# impulse.net
KiCad netlist of a schematic drawn in Altium Designer
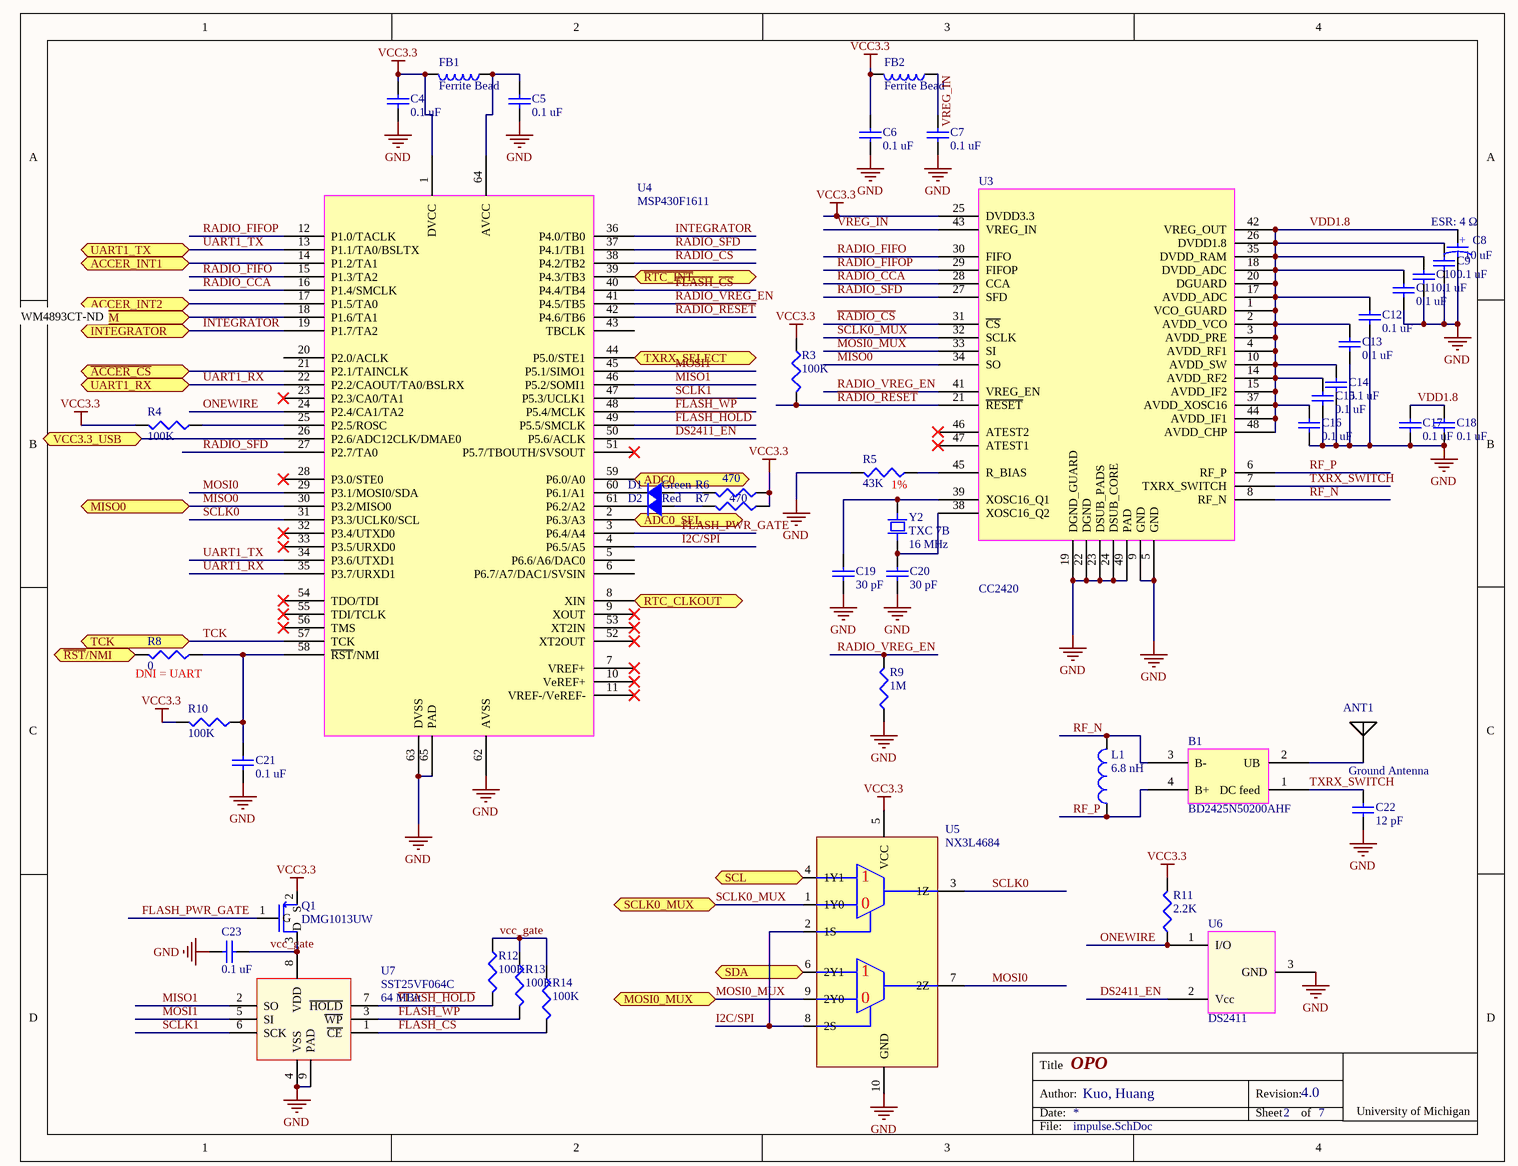
[diagram p0: impulse.SchDoc]

(export (version "E")
  (design (tool "Eeschema 10.0.6"))
  (components
    (comp (ref "ANT1")
      (value "Ground Antenna")
      (footprint "Chip Antenna")
      (description "2.4GHz Surface Mount Device (SMD) On Ground Antenna, 50 Ohms")
      (libsource (lib "opo") (part "Ground Antenna"))
    )
    (comp (ref "B1")
      (value "BD2425N50200AHF")
      (footprint "BD2425N50200AHF")
      (description "Ultra Low Profile 0404 Balun   50Ω to 200Ω Balanced")
      (libsource (lib "opo") (part "BD2425N50200AHF"))
    )
    (comp (ref "C4")
      (value "0.1 uF")
      (footprint "0402")
      (description "Ceramic capacitor, 0.1u, 0402 package")
      (fields (field (name "TOLERANCE") "10%") (field (name "Comment") "Ceramic capacitor"))
      (libsource (lib "rlc") (part "C_0.1u_0402_ceramic"))
    )
    (comp (ref "C5")
      (value "0.1 uF")
      (footprint "0402")
      (description "Ceramic capacitor, 0.1u, 0402 package")
      (fields (field (name "TOLERANCE") "10%") (field (name "Comment") "Ceramic capacitor"))
      (libsource (lib "rlc") (part "C_0.1u_0402_ceramic"))
    )
    (comp (ref "C6")
      (value "0.1 uF")
      (footprint "0402")
      (description "Ceramic capacitor, 0.1u, 0402 package")
      (fields (field (name "TOLERANCE") "10%") (field (name "Comment") "Ceramic capacitor"))
      (libsource (lib "rlc") (part "C_0.1u_0402_ceramic"))
    )
    (comp (ref "C7")
      (value "0.1 uF")
      (footprint "0402")
      (description "Ceramic capacitor, 0.1u, 0402 package")
      (fields (field (name "TOLERANCE") "10%") (field (name "Comment") "Ceramic capacitor"))
      (libsource (lib "rlc") (part "C_0.1u_0402_ceramic"))
    )
    (comp (ref "C8")
      (value "10 uF")
      (footprint "0603 - Polar Marking")
      (description "Tantalum capacitor, 10 uF, 0603 package")
      (fields
        (field (name "TOLERANCE") "10%")
        (field (name "ESR") "4 Ω")
        (field (name "Comment") "Tantalum capacitor")
      )
      (libsource (lib "rlc") (part "C_10u_0603_tantalum"))
    )
    (comp (ref "C9")
      (value "0.1 uF")
      (footprint "0402")
      (description "Ceramic capacitor, 0.1u, 0402 package")
      (fields (field (name "TOLERANCE") "10%") (field (name "Comment") "Ceramic capacitor"))
      (libsource (lib "rlc") (part "C_0.1u_0402_ceramic"))
    )
    (comp (ref "C10")
      (value "0.1 uF")
      (footprint "0402")
      (description "Ceramic capacitor, 0.1u, 0402 package")
      (fields (field (name "TOLERANCE") "10%") (field (name "Comment") "Ceramic capacitor"))
      (libsource (lib "rlc") (part "C_0.1u_0402_ceramic"))
    )
    (comp (ref "C11")
      (value "0.1 uF")
      (footprint "0402")
      (description "Ceramic capacitor, 0.1u, 0402 package")
      (fields (field (name "TOLERANCE") "10%") (field (name "Comment") "Ceramic capacitor"))
      (libsource (lib "rlc") (part "C_0.1u_0402_ceramic"))
    )
    (comp (ref "C12")
      (value "0.1 uF")
      (footprint "0402")
      (description "Ceramic capacitor, 0.1u, 0402 package")
      (fields (field (name "TOLERANCE") "10%") (field (name "Comment") "Ceramic capacitor"))
      (libsource (lib "rlc") (part "C_0.1u_0402_ceramic"))
    )
    (comp (ref "C13")
      (value "0.1 uF")
      (footprint "0402")
      (description "Ceramic capacitor, 0.1u, 0402 package")
      (fields (field (name "TOLERANCE") "10%") (field (name "Comment") "Ceramic capacitor"))
      (libsource (lib "rlc") (part "C_0.1u_0402_ceramic"))
    )
    (comp (ref "C14")
      (value "0.1 uF")
      (footprint "0402")
      (description "Ceramic capacitor, 0.1u, 0402 package")
      (fields (field (name "TOLERANCE") "10%") (field (name "Comment") "Ceramic capacitor"))
      (libsource (lib "rlc") (part "C_0.1u_0402_ceramic"))
    )
    (comp (ref "C15")
      (value "0.1 uF")
      (footprint "0402")
      (description "Ceramic capacitor, 0.1u, 0402 package")
      (fields (field (name "TOLERANCE") "10%") (field (name "Comment") "Ceramic capacitor"))
      (libsource (lib "rlc") (part "C_0.1u_0402_ceramic"))
    )
    (comp (ref "C16")
      (value "0.1 uF")
      (footprint "0402")
      (description "Ceramic capacitor, 0.1u, 0402 package")
      (fields (field (name "TOLERANCE") "10%") (field (name "Comment") "Ceramic capacitor"))
      (libsource (lib "rlc") (part "C_0.1u_0402_ceramic"))
    )
    (comp (ref "C17")
      (value "0.1 uF")
      (footprint "0402")
      (description "Ceramic capacitor, 0.1u, 0402 package")
      (fields (field (name "TOLERANCE") "10%") (field (name "Comment") "Ceramic capacitor"))
      (libsource (lib "rlc") (part "C_0.1u_0402_ceramic"))
    )
    (comp (ref "C18")
      (value "0.1 uF")
      (footprint "0402")
      (description "Ceramic capacitor, 0.1u, 0402 package")
      (fields (field (name "TOLERANCE") "10%") (field (name "Comment") "Ceramic capacitor"))
      (libsource (lib "rlc") (part "C_0.1u_0402_ceramic"))
    )
    (comp (ref "C19")
      (value "30 pF")
      (footprint "0402")
      (description "Ceramic capacitor, 30 pF, 0402 package")
      (fields (field (name "TOLERANCE") "2%") (field (name "Comment") "Ceramic capacitor"))
      (libsource (lib "rlc") (part "C_30p_0402_ceramic"))
    )
    (comp (ref "C20")
      (value "30 pF")
      (footprint "0402")
      (description "Ceramic capacitor, 30 pF, 0402 package")
      (fields (field (name "TOLERANCE") "2%") (field (name "Comment") "Ceramic capacitor"))
      (libsource (lib "rlc") (part "C_30p_0402_ceramic"))
    )
    (comp (ref "C21")
      (value "0.1 uF")
      (footprint "0402")
      (description "Ceramic capacitor, 0.1u, 0402 package")
      (fields (field (name "TOLERANCE") "10%") (field (name "Comment") "Ceramic capacitor"))
      (libsource (lib "rlc") (part "C_0.1u_0402_ceramic"))
    )
    (comp (ref "C22")
      (value "12 pF")
      (footprint "0402")
      (description "Ceramic capacitor, 12 pF, 0402 package")
      (fields (field (name "TOLERANCE") "2%") (field (name "Comment") "Ceramic capacitor"))
      (libsource (lib "rlc") (part "C_12p_0402_ceramic"))
    )
    (comp (ref "C23")
      (value "0.1 uF")
      (footprint "0402")
      (description "Ceramic capacitor, 0.1u, 0402 package")
      (fields (field (name "TOLERANCE") "10%") (field (name "Comment") "Ceramic capacitor"))
      (libsource (lib "rlc") (part "C_0.1u_0402_ceramic"))
    )
    (comp (ref "D1")
      (value "LED, Green")
      (footprint "0402 - DIODE")
      (description "LED, Green,  0402")
      (fields (field (name "COLOR") "Green"))
      (libsource (lib "rlc") (part "D_LED_GREEN_0402"))
    )
    (comp (ref "D2")
      (value "LED, Red")
      (footprint "0402 - DIODE")
      (description "LED, Red, 0402")
      (fields (field (name "COLOR") "Red"))
      (libsource (lib "rlc") (part "D_LED_RED_0402"))
    )
    (comp (ref "FB1")
      (value "Ferrite Bead")
      (footprint "0402")
      (description "Ferrite Bead, 150 mA, 0402 package")
      (libsource (lib "rlc") (part "FB_150mA_0402"))
    )
    (comp (ref "FB2")
      (value "Ferrite Bead")
      (footprint "0402")
      (description "Ferrite Bead, 150 mA, 0402 package")
      (libsource (lib "rlc") (part "FB_150mA_0402"))
    )
    (comp (ref "L1")
      (value "6.8 nH")
      (footprint "0402")
      (description "Chip inductor, 6.8 nH, 0402 package")
      (fields (field (name "TOLERANCE") "5%") (field (name "Comment") "Chip inductor"))
      (libsource (lib "rlc") (part "L_6.8n_0402"))
    )
    (comp (ref "Q1")
      (value "DMG1013UW")
      (footprint "SC70-3")
      (description "P-CHANNEL ENHANCEMENT MODE MOSFET")
      (libsource (lib "opo") (part "DMG1013UW"))
    )
    (comp (ref "R3")
      (value "100K")
      (footprint "0402")
      (description "Chip resistor, 100K, 0402 package")
      (fields (field (name "TOLERANCE") "1%") (field (name "POWER") "1/16 W"))
      (libsource (lib "rlc") (part "R_100K_0402"))
    )
    (comp (ref "R4")
      (value "100K")
      (footprint "0402")
      (description "Chip resistor, 100K, 0402 package")
      (fields (field (name "TOLERANCE") "1%") (field (name "POWER") "1/16 W"))
      (libsource (lib "rlc") (part "R_100K_0402"))
    )
    (comp (ref "R5")
      (value "43K")
      (footprint "0402")
      (description "Chip resistor, 43K, 0402 package")
      (fields (field (name "TOLERANCE") "1%") (field (name "POWER") "1/16 W"))
      (libsource (lib "rlc") (part "R_43K_0402"))
    )
    (comp (ref "R6")
      (value "470")
      (footprint "0402")
      (description "Chip resistor, 470, 0402 package")
      (fields (field (name "TOLERANCE") "1%") (field (name "POWER") "1/16 W"))
      (libsource (lib "rlc") (part "R_470_0402"))
    )
    (comp (ref "R7")
      (value "470")
      (footprint "0402")
      (description "Chip resistor, 470, 0402 package")
      (fields (field (name "TOLERANCE") "1%") (field (name "POWER") "1/16 W"))
      (libsource (lib "rlc") (part "R_470_0402"))
    )
    (comp (ref "R8")
      (value "0")
      (footprint "0402")
      (description "Chip resistor, 0, 0402 package")
      (fields (field (name "Comment") "Chip resistor"))
      (libsource (lib "rlc") (part "R_0_0402"))
    )
    (comp (ref "R9")
      (value "1M")
      (footprint "0402")
      (description "Chip resistor, 1M, 0402 package")
      (fields (field (name "TOLERANCE") "1%") (field (name "POWER") "1/16 W"))
      (libsource (lib "rlc") (part "R_1M_0402"))
    )
    (comp (ref "R10")
      (value "100K")
      (footprint "0402")
      (description "Chip resistor, 100K, 0402 package")
      (fields (field (name "TOLERANCE") "1%") (field (name "POWER") "1/16 W"))
      (libsource (lib "rlc") (part "R_100K_0402"))
    )
    (comp (ref "R11")
      (value "2.2K")
      (footprint "0402")
      (description "Chip resistor, 2.2K, 0402 package")
      (fields (field (name "TOLERANCE") "1%") (field (name "POWER") "1/16 W"))
      (libsource (lib "rlc") (part "R_2.2K_0402"))
    )
    (comp (ref "R12")
      (value "100K")
      (footprint "0402")
      (description "Chip resistor, 100K, 0402 package")
      (fields (field (name "TOLERANCE") "1%") (field (name "POWER") "1/16 W"))
      (libsource (lib "rlc") (part "R_100K_0402"))
    )
    (comp (ref "R13")
      (value "100K")
      (footprint "0402")
      (description "Chip resistor, 100K, 0402 package")
      (fields (field (name "TOLERANCE") "1%") (field (name "POWER") "1/16 W"))
      (libsource (lib "rlc") (part "R_100K_0402"))
    )
    (comp (ref "R14")
      (value "100K")
      (footprint "0402")
      (description "Chip resistor, 100K, 0402 package")
      (fields (field (name "TOLERANCE") "1%") (field (name "POWER") "1/16 W"))
      (libsource (lib "rlc") (part "R_100K_0402"))
    )
    (comp (ref "U3")
      (value "CC2420")
      (footprint "QFN50P700X700X100_HS-49N")
      (description "2.4 GHz IEEE 802.15.4 / ZigBee-ready RF Transceiver")
      (libsource (lib "opo") (part "CC2420"))
    )
    (comp (ref "U4")
      (value "MSP430F1611")
      (footprint "QFN50P900X900X90_HS-65N")
      (description "MIXED SIGNAL MICROCONTROLLER")
      (libsource (lib "opo") (part "MSP430F1611"))
    )
    (comp (ref "U5")
      (value "NX3L4684")
      (footprint "QFN50P155X200X13-10N")
      (description "IC ANALOG SWITCH SPDT 10XQFN")
      (libsource (lib "opo") (part "NX3L4684"))
    )
    (comp (ref "U6")
      (value "DS2411")
      (footprint "SOT23-3N")
      (description "Silicon Serial Number with VCC Input")
      (libsource (lib "opo") (part "DS2411"))
    )
    (comp (ref "U7")
      (value "SST25VF064C")
      (footprint "WSON")
      (description "64 Mbit SPI Serial Dual I/O Flash")
      (fields (field (name "CAPACITY") "64 MBit"))
      (libsource (lib "opo") (part "SST25VF064C"))
    )
    (comp (ref "Y2")
      (value "TXC 7B")
      (footprint "TXC 7B")
      (description "5 x 3.2 mm SMD SEAM CRYSTAL 7B SERIES")
      (fields (field (name "FREQUENCY") "16 MHz"))
      (libsource (lib "opo") (part "TXC 7B"))
    )
  )
  (nets
    (net (code "1") (name "/ACCER_INT1") (class "Default")
      (node (ref "U4") (pin "14") (pinfunction "P1.2/TA1_14") (pintype "passive"))
    )
    (net (code "2") (name "/ACCER_INT2") (class "Default")
      (node (ref "U4") (pin "17") (pinfunction "P1.5/TA0_17") (pintype "passive"))
    )
    (net (code "3") (name "/ADC0") (class "Default")
      (node (ref "U4") (pin "59") (pinfunction "P6.0/A0_59") (pintype "passive"))
    )
    (net (code "4") (name "/ADC0_SEL") (class "Default")
      (node (ref "U4") (pin "2") (pinfunction "P6.3/A3_2") (pintype "passive"))
    )
    (net (code "5") (name "/DS2411_EN") (class "Default")
      (node (ref "U4") (pin "50") (pinfunction "P5.6/ACLK_50") (pintype "passive"))
      (node (ref "U6") (pin "2") (pinfunction "Vcc_2") (pintype "passive"))
    )
    (net (code "6") (name "/FLASH_PWR_GATE") (class "Default")
      (node (ref "Q1") (pin "1") (pinfunction "G_1") (pintype "passive"))
      (node (ref "U4") (pin "3") (pinfunction "P6.4/A4_3") (pintype "passive"))
    )
    (net (code "7") (name "/I2C{slash}SPI") (class "Default")
      (node (ref "U4") (pin "4") (pinfunction "P6.5/A5_4") (pintype "passive"))
      (node (ref "U5") (pin "2") (pinfunction "1S_2") (pintype "passive"))
      (node (ref "U5") (pin "8") (pinfunction "2S_8") (pintype "passive"))
    )
    (net (code "8") (name "/INTEGRATOR") (class "Default")
      (node (ref "U4") (pin "19") (pinfunction "P1.7/TA2_19") (pintype "passive"))
      (node (ref "U4") (pin "36") (pinfunction "P4.0/TB0_36") (pintype "passive"))
    )
    (net (code "9") (name "/MISO0") (class "Default")
      (node (ref "U3") (pin "34") (pinfunction "SO_34") (pintype "passive"))
      (node (ref "U4") (pin "30") (pinfunction "P3.2/MISO0_30") (pintype "passive"))
    )
    (net (code "10") (name "/MISO1") (class "Default")
      (node (ref "U4") (pin "46") (pinfunction "P5.2/SOMI1_46") (pintype "passive"))
      (node (ref "U7") (pin "2") (pinfunction "SO_2") (pintype "passive"))
    )
    (net (code "11") (name "/MOSI0") (class "Default")
      (node (ref "U4") (pin "29") (pinfunction "P3.1/MOSI0/SDA_29") (pintype "passive"))
      (node (ref "U5") (pin "7") (pinfunction "2Z_7") (pintype "passive"))
    )
    (net (code "12") (name "/MOSI0_MUX") (class "Default")
      (node (ref "U3") (pin "33") (pinfunction "SI_33") (pintype "passive"))
      (node (ref "U5") (pin "9") (pinfunction "2Y0_9") (pintype "passive"))
    )
    (net (code "13") (name "/MOSI1") (class "Default")
      (node (ref "U4") (pin "45") (pinfunction "P5.1/SIMO1_45") (pintype "passive"))
      (node (ref "U7") (pin "5") (pinfunction "SI_5") (pintype "passive"))
    )
    (net (code "14") (name "/ONEWIRE") (class "Default")
      (node (ref "R11") (pin "2") (pintype "passive"))
      (node (ref "U4") (pin "24") (pinfunction "P2.4/CA1/TA2_24") (pintype "passive"))
      (node (ref "U6") (pin "1") (pinfunction "I/O_1") (pintype "passive"))
    )
    (net (code "15") (name "/PWM") (class "Default")
      (node (ref "U4") (pin "18") (pinfunction "P1.6/TA1_18") (pintype "passive"))
    )
    (net (code "16") (name "/RADIO_CCA") (class "Default")
      (node (ref "U3") (pin "28") (pinfunction "CCA_28") (pintype "passive"))
      (node (ref "U4") (pin "16") (pinfunction "P1.4/SMCLK_16") (pintype "passive"))
    )
    (net (code "17") (name "/RADIO_FIFO") (class "Default")
      (node (ref "U3") (pin "30") (pinfunction "FIFO_30") (pintype "passive"))
      (node (ref "U4") (pin "15") (pinfunction "P1.3/TA2_15") (pintype "passive"))
    )
    (net (code "18") (name "/RADIO_FIFOP") (class "Default")
      (node (ref "U3") (pin "29") (pinfunction "FIFOP_29") (pintype "passive"))
      (node (ref "U4") (pin "12") (pinfunction "P1.0/TACLK_12") (pintype "passive"))
    )
    (net (code "19") (name "/RADIO_SFD") (class "Default")
      (node (ref "U3") (pin "27") (pinfunction "SFD_27") (pintype "passive"))
      (node (ref "U4") (pin "27") (pinfunction "P2.7/TA0_27") (pintype "passive"))
      (node (ref "U4") (pin "37") (pinfunction "P4.1/TB1_37") (pintype "passive"))
    )
    (net (code "20") (name "/RADIO_VREG_EN") (class "Default")
      (node (ref "R9") (pin "1") (pintype "passive"))
      (node (ref "U3") (pin "41") (pinfunction "VREG_EN_41") (pintype "passive"))
      (node (ref "U4") (pin "41") (pinfunction "P4.5/TB5_41") (pintype "passive"))
    )
    (net (code "21") (name "/RF_N") (class "Default")
      (node (ref "B1") (pin "3") (pinfunction "B-_3") (pintype "passive"))
      (node (ref "L1") (pin "1") (pintype "passive"))
      (node (ref "U3") (pin "8") (pinfunction "RF_N_8") (pintype "passive"))
    )
    (net (code "22") (name "/RF_P") (class "Default")
      (node (ref "B1") (pin "4") (pinfunction "B+_4") (pintype "passive"))
      (node (ref "L1") (pin "2") (pintype "passive"))
      (node (ref "U3") (pin "6") (pinfunction "RF_P_6") (pintype "passive"))
    )
    (net (code "23") (name "/RTC_CLKOUT") (class "Default")
      (node (ref "U4") (pin "8") (pinfunction "XIN_8") (pintype "passive"))
    )
    (net (code "24") (name "/SCL") (class "Default")
      (node (ref "U5") (pin "4") (pinfunction "1Y1_4") (pintype "passive"))
    )
    (net (code "25") (name "/SCLK0") (class "Default")
      (node (ref "U4") (pin "31") (pinfunction "P3.3/UCLK0/SCL_31") (pintype "passive"))
      (node (ref "U5") (pin "3") (pinfunction "1Z_3") (pintype "passive"))
    )
    (net (code "26") (name "/SCLK0_MUX") (class "Default")
      (node (ref "U3") (pin "32") (pinfunction "SCLK_32") (pintype "passive"))
      (node (ref "U5") (pin "1") (pinfunction "1Y0_1") (pintype "passive"))
    )
    (net (code "27") (name "/SCLK1") (class "Default")
      (node (ref "U4") (pin "47") (pinfunction "P5.3/UCLK1_47") (pintype "passive"))
      (node (ref "U7") (pin "6") (pinfunction "SCK_6") (pintype "passive"))
    )
    (net (code "28") (name "/SDA") (class "Default")
      (node (ref "U5") (pin "6") (pinfunction "2Y1_6") (pintype "passive"))
    )
    (net (code "29") (name "/TCK") (class "Default")
      (node (ref "U4") (pin "57") (pinfunction "TCK_57") (pintype "passive"))
    )
    (net (code "30") (name "/TXRX_SELECT") (class "Default")
      (node (ref "U4") (pin "44") (pinfunction "P5.0/STE1_44") (pintype "passive"))
    )
    (net (code "31") (name "/TXRX_SWITCH") (class "Default")
      (node (ref "B1") (pin "1") (pinfunction "DC_feed_1") (pintype "passive"))
      (node (ref "C22") (pin "1") (pintype "passive"))
      (node (ref "U3") (pin "7") (pinfunction "TXRX_SWITCH_7") (pintype "passive"))
    )
    (net (code "32") (name "/UART1_RX") (class "Default")
      (node (ref "U4") (pin "22") (pinfunction "P2.2/CAOUT/TA0/BSLRX_22") (pintype "passive"))
      (node (ref "U4") (pin "35") (pinfunction "P3.7/URXD1_35") (pintype "passive"))
    )
    (net (code "33") (name "/UART1_TX") (class "Default")
      (node (ref "U4") (pin "13") (pinfunction "P1.1/TA0/BSLTX_13") (pintype "passive"))
      (node (ref "U4") (pin "34") (pinfunction "P3.6/UTXD1_34") (pintype "passive"))
    )
    (net (code "34") (name "/VCC3.3_USB") (class "Default")
      (node (ref "U4") (pin "26") (pinfunction "P2.6/ADC12CLK/DMAE0_26") (pintype "passive"))
    )
    (net (code "35") (name "/VDD1.8") (class "Default")
      (node (ref "C10") (pin "1") (pintype "passive"))
      (node (ref "C11") (pin "1") (pintype "passive"))
      (node (ref "C12") (pin "1") (pintype "passive"))
      (node (ref "C13") (pin "1") (pintype "passive"))
      (node (ref "C14") (pin "1") (pintype "passive"))
      (node (ref "C15") (pin "1") (pintype "passive"))
      (node (ref "C16") (pin "1") (pintype "passive"))
      (node (ref "C17") (pin "1") (pintype "passive"))
      (node (ref "C18") (pin "1") (pintype "passive"))
      (node (ref "C8") (pin "1") (pintype "passive"))
      (node (ref "C9") (pin "1") (pintype "passive"))
      (node (ref "U3") (pin "1") (pinfunction "VCO_GUARD_1") (pintype "passive"))
      (node (ref "U3") (pin "10") (pinfunction "AVDD_SW_10") (pintype "passive"))
      (node (ref "U3") (pin "14") (pinfunction "AVDD_RF2_14") (pintype "passive"))
      (node (ref "U3") (pin "15") (pinfunction "AVDD_IF2_15") (pintype "passive"))
      (node (ref "U3") (pin "17") (pinfunction "AVDD_ADC_17") (pintype "passive"))
      (node (ref "U3") (pin "18") (pinfunction "DVDD_ADC_18") (pintype "passive"))
      (node (ref "U3") (pin "2") (pinfunction "AVDD_VCO_2") (pintype "passive"))
      (node (ref "U3") (pin "20") (pinfunction "DGUARD_20") (pintype "passive"))
      (node (ref "U3") (pin "26") (pinfunction "DVDD1.8_26") (pintype "passive"))
      (node (ref "U3") (pin "3") (pinfunction "AVDD_PRE_3") (pintype "passive"))
      (node (ref "U3") (pin "35") (pinfunction "DVDD_RAM_35") (pintype "passive"))
      (node (ref "U3") (pin "37") (pinfunction "AVDD_XOSC16_37") (pintype "passive"))
      (node (ref "U3") (pin "4") (pinfunction "AVDD_RF1_4") (pintype "passive"))
      (node (ref "U3") (pin "42") (pinfunction "VREG_OUT_42") (pintype "passive"))
      (node (ref "U3") (pin "44") (pinfunction "AVDD_IF1_44") (pintype "passive"))
      (node (ref "U3") (pin "48") (pinfunction "AVDD_CHP_48") (pintype "passive"))
    )
    (net (code "36") (name "/VREG_IN") (class "Default")
      (node (ref "C7") (pin "1") (pintype "passive"))
      (node (ref "FB2") (pin "2") (pintype "passive"))
      (node (ref "U3") (pin "43") (pinfunction "VREG_IN_43") (pintype "passive"))
    )
    (net (code "37") (name "/vcc_gate") (class "Default")
      (node (ref "C23") (pin "1") (pintype "passive"))
      (node (ref "Q1") (pin "3") (pinfunction "D_3") (pintype "passive"))
      (node (ref "R12") (pin "2") (pintype "passive"))
      (node (ref "R13") (pin "2") (pintype "passive"))
      (node (ref "R14") (pin "2") (pintype "passive"))
      (node (ref "U7") (pin "8") (pinfunction "VDD_8") (pintype "passive"))
    )
    (net (code "38") (name "/~{ACCER_CS}") (class "Default")
      (node (ref "U4") (pin "21") (pinfunction "P2.1/TAINCLK_21") (pintype "passive"))
    )
    (net (code "39") (name "/~{FLASH_HOLD}") (class "Default")
      (node (ref "R12") (pin "1") (pintype "passive"))
      (node (ref "U4") (pin "49") (pinfunction "P5.5/SMCLK_49") (pintype "passive"))
      (node (ref "U7") (pin "7") (pinfunction "~{HOLD}_7") (pintype "passive"))
    )
    (net (code "40") (name "/~{FLASH_WP}") (class "Default")
      (node (ref "R13") (pin "1") (pintype "passive"))
      (node (ref "U4") (pin "48") (pinfunction "P5.4/MCLK_48") (pintype "passive"))
      (node (ref "U7") (pin "3") (pinfunction "~{WP}_3") (pintype "passive"))
    )
    (net (code "41") (name "/~{FLASH}_~{CS}") (class "Default")
      (node (ref "R14") (pin "1") (pintype "passive"))
      (node (ref "U4") (pin "40") (pinfunction "P4.4/TB4_40") (pintype "passive"))
      (node (ref "U7") (pin "1") (pinfunction "~{CE}_1") (pintype "passive"))
    )
    (net (code "42") (name "/~{RADIO_CS}") (class "Default")
      (node (ref "U3") (pin "31") (pinfunction "~{CS}_31") (pintype "passive"))
      (node (ref "U4") (pin "38") (pinfunction "P4.2/TB2_38") (pintype "passive"))
    )
    (net (code "43") (name "/~{RADIO_RESET}") (class "Default")
      (node (ref "R3") (pin "1") (pintype "passive"))
      (node (ref "U3") (pin "21") (pinfunction "~{RESET}_21") (pintype "passive"))
      (node (ref "U4") (pin "42") (pinfunction "P4.6/TB6_42") (pintype "passive"))
    )
    (net (code "44") (name "/~{RST}{slash}NMI") (class "Default")
      (node (ref "R8") (pin "1") (pintype "passive"))
    )
    (net (code "45") (name "/~{RTC_INT}") (class "Default")
      (node (ref "U4") (pin "39") (pinfunction "P4.3/TB3_39") (pintype "passive"))
    )
    (net (code "46") (name "GND") (class "Default")
      (node (ref "C10") (pin "2") (pintype "passive"))
      (node (ref "C11") (pin "2") (pintype "passive"))
      (node (ref "C12") (pin "2") (pintype "passive"))
      (node (ref "C13") (pin "2") (pintype "passive"))
      (node (ref "C14") (pin "2") (pintype "passive"))
      (node (ref "C15") (pin "2") (pintype "passive"))
      (node (ref "C16") (pin "2") (pintype "passive"))
      (node (ref "C17") (pin "2") (pintype "passive"))
      (node (ref "C18") (pin "2") (pintype "passive"))
      (node (ref "C19") (pin "1") (pintype "passive"))
      (node (ref "C20") (pin "1") (pintype "passive"))
      (node (ref "C21") (pin "2") (pintype "passive"))
      (node (ref "C22") (pin "2") (pintype "passive"))
      (node (ref "C23") (pin "2") (pintype "passive"))
      (node (ref "C4") (pin "2") (pintype "passive"))
      (node (ref "C5") (pin "2") (pintype "passive"))
      (node (ref "C6") (pin "2") (pintype "passive"))
      (node (ref "C7") (pin "2") (pintype "passive"))
      (node (ref "C8") (pin "2") (pintype "passive"))
      (node (ref "C9") (pin "2") (pintype "passive"))
      (node (ref "R5") (pin "1") (pintype "passive"))
      (node (ref "R9") (pin "2") (pintype "passive"))
      (node (ref "U3") (pin "19") (pinfunction "DGND_GUARD_19") (pintype "passive"))
      (node (ref "U3") (pin "22") (pinfunction "DGND_22") (pintype "passive"))
      (node (ref "U3") (pin "23") (pinfunction "DSUB_PADS_23") (pintype "passive"))
      (node (ref "U3") (pin "24") (pinfunction "DSUB_CORE_24") (pintype "passive"))
      (node (ref "U3") (pin "49") (pinfunction "PAD_49") (pintype "passive"))
      (node (ref "U3") (pin "5") (pinfunction "GND_5") (pintype "passive"))
      (node (ref "U3") (pin "9") (pinfunction "GND_9") (pintype "passive"))
      (node (ref "U4") (pin "62") (pinfunction "AVSS_62") (pintype "passive"))
      (node (ref "U4") (pin "63") (pinfunction "DVSS_63") (pintype "passive"))
      (node (ref "U4") (pin "65") (pinfunction "PAD_65") (pintype "passive"))
      (node (ref "U5") (pin "10") (pinfunction "GND_10") (pintype "passive"))
      (node (ref "U6") (pin "3") (pinfunction "GND_3") (pintype "passive"))
      (node (ref "U7") (pin "4") (pinfunction "VSS_4") (pintype "passive"))
      (node (ref "U7") (pin "9") (pinfunction "PAD_9") (pintype "passive"))
    )
    (net (code "47") (name "Net-(B1-UB)") (class "Default")
      (node (ref "ANT1") (pin "1") (pintype "passive"))
      (node (ref "B1") (pin "2") (pinfunction "UB_2") (pintype "passive"))
    )
    (net (code "48") (name "Net-(D1-Pad1)") (class "Default")
      (node (ref "D1") (pin "1") (pintype "passive"))
      (node (ref "R6") (pin "1") (pintype "passive"))
    )
    (net (code "49") (name "Net-(D2-Pad1)") (class "Default")
      (node (ref "D2") (pin "1") (pintype "passive"))
      (node (ref "R7") (pin "1") (pintype "passive"))
    )
    (net (code "50") (name "Net-(U3-R_BIAS)") (class "Default")
      (node (ref "R5") (pin "2") (pintype "passive"))
      (node (ref "U3") (pin "45") (pinfunction "R_BIAS_45") (pintype "passive"))
    )
    (net (code "51") (name "Net-(U3-XOSC16_Q1)") (class "Default")
      (node (ref "C19") (pin "2") (pintype "passive"))
      (node (ref "U3") (pin "39") (pinfunction "XOSC16_Q1_39") (pintype "passive"))
      (node (ref "Y2") (pin "1") (pintype "passive"))
    )
    (net (code "52") (name "Net-(U3-XOSC16_Q2)") (class "Default")
      (node (ref "C20") (pin "2") (pintype "passive"))
      (node (ref "U3") (pin "38") (pinfunction "XOSC16_Q2_38") (pintype "passive"))
      (node (ref "Y2") (pin "3") (pintype "passive"))
    )
    (net (code "53") (name "Net-(U4-AVCC)") (class "Default")
      (node (ref "C5") (pin "1") (pintype "passive"))
      (node (ref "FB1") (pin "2") (pintype "passive"))
      (node (ref "U4") (pin "64") (pinfunction "AVCC_64") (pintype "passive"))
    )
    (net (code "54") (name "Net-(U4-P2.5{slash}ROSC)") (class "Default")
      (node (ref "R4") (pin "2") (pintype "passive"))
      (node (ref "U4") (pin "25") (pinfunction "P2.5/ROSC_25") (pintype "passive"))
    )
    (net (code "55") (name "Net-(U4-P6.1{slash}A1)") (class "Default")
      (node (ref "D1") (pin "2") (pintype "passive"))
      (node (ref "U4") (pin "60") (pinfunction "P6.1/A1_60") (pintype "passive"))
    )
    (net (code "56") (name "Net-(U4-P6.2{slash}A2)") (class "Default")
      (node (ref "D2") (pin "2") (pintype "passive"))
      (node (ref "U4") (pin "61") (pinfunction "P6.2/A2_61") (pintype "passive"))
    )
    (net (code "57") (name "Net-(U4-~{RST}{slash}NMI)") (class "Default")
      (node (ref "C21") (pin "1") (pintype "passive"))
      (node (ref "R10") (pin "2") (pintype "passive"))
      (node (ref "R8") (pin "2") (pintype "passive"))
      (node (ref "U4") (pin "58") (pinfunction "~{RST}/NMI_58") (pintype "passive"))
    )
    (net (code "58") (name "VCC3.3") (class "Default")
      (node (ref "C4") (pin "1") (pintype "passive"))
      (node (ref "C6") (pin "1") (pintype "passive"))
      (node (ref "FB1") (pin "1") (pintype "passive"))
      (node (ref "FB2") (pin "1") (pintype "passive"))
      (node (ref "Q1") (pin "2") (pinfunction "S_2") (pintype "passive"))
      (node (ref "R10") (pin "1") (pintype "passive"))
      (node (ref "R11") (pin "1") (pintype "passive"))
      (node (ref "R3") (pin "2") (pintype "passive"))
      (node (ref "R4") (pin "1") (pintype "passive"))
      (node (ref "R6") (pin "2") (pintype "passive"))
      (node (ref "R7") (pin "2") (pintype "passive"))
      (node (ref "U3") (pin "25") (pinfunction "DVDD3.3_25") (pintype "passive"))
      (node (ref "U4") (pin "1") (pinfunction "DVCC_1") (pintype "passive"))
      (node (ref "U5") (pin "5") (pinfunction "VCC_5") (pintype "passive"))
    )
    (net (code "59") (name "unconnected-(U3-ATEST1-Pad47)") (class "Default")
      (node (ref "U3") (pin "47") (pinfunction "ATEST1_47") (pintype "passive+no_connect"))
    )
    (net (code "60") (name "unconnected-(U3-ATEST2-Pad46)") (class "Default")
      (node (ref "U3") (pin "46") (pinfunction "ATEST2_46") (pintype "passive+no_connect"))
    )
    (net (code "61") (name "unconnected-(U4-P2.0{slash}ACLK-Pad20)") (class "Default")
      (node (ref "U4") (pin "20") (pinfunction "P2.0/ACLK_20") (pintype "passive"))
    )
    (net (code "62") (name "unconnected-(U4-P2.3{slash}CA0{slash}TA1-Pad23)") (class "Default")
      (node (ref "U4") (pin "23") (pinfunction "P2.3/CA0/TA1_23") (pintype "passive+no_connect"))
    )
    (net (code "63") (name "unconnected-(U4-P3.0{slash}STE0-Pad28)") (class "Default")
      (node (ref "U4") (pin "28") (pinfunction "P3.0/STE0_28") (pintype "passive+no_connect"))
    )
    (net (code "64") (name "unconnected-(U4-P3.4{slash}UTXD0-Pad32)") (class "Default")
      (node (ref "U4") (pin "32") (pinfunction "P3.4/UTXD0_32") (pintype "passive+no_connect"))
    )
    (net (code "65") (name "unconnected-(U4-P3.5{slash}URXD0-Pad33)") (class "Default")
      (node (ref "U4") (pin "33") (pinfunction "P3.5/URXD0_33") (pintype "passive+no_connect"))
    )
    (net (code "66") (name "unconnected-(U4-P5.7{slash}TBOUTH{slash}SVSOUT-Pad51)") (class "Default")
      (node (ref "U4") (pin "51") (pinfunction "P5.7/TBOUTH/SVSOUT_51") (pintype "passive+no_connect"))
    )
    (net (code "67") (name "unconnected-(U4-P6.6{slash}A6{slash}DAC0-Pad5)") (class "Default")
      (node (ref "U4") (pin "5") (pinfunction "P6.6/A6/DAC0_5") (pintype "passive"))
    )
    (net (code "68") (name "unconnected-(U4-P6.7{slash}A7{slash}DAC1{slash}SVSIN-Pad6)") (class "Default")
      (node (ref "U4") (pin "6") (pinfunction "P6.7/A7/DAC1/SVSIN_6") (pintype "passive"))
    )
    (net (code "69") (name "unconnected-(U4-TBCLK-Pad43)") (class "Default")
      (node (ref "U4") (pin "43") (pinfunction "TBCLK_43") (pintype "passive"))
    )
    (net (code "70") (name "unconnected-(U4-TDI{slash}TCLK-Pad55)") (class "Default")
      (node (ref "U4") (pin "55") (pinfunction "TDI/TCLK_55") (pintype "passive+no_connect"))
    )
    (net (code "71") (name "unconnected-(U4-TDO{slash}TDI-Pad54)") (class "Default")
      (node (ref "U4") (pin "54") (pinfunction "TDO/TDI_54") (pintype "passive+no_connect"))
    )
    (net (code "72") (name "unconnected-(U4-TMS-Pad56)") (class "Default")
      (node (ref "U4") (pin "56") (pinfunction "TMS_56") (pintype "passive+no_connect"))
    )
    (net (code "73") (name "unconnected-(U4-VREF+-Pad7)") (class "Default")
      (node (ref "U4") (pin "7") (pinfunction "VREF+_7") (pintype "passive+no_connect"))
    )
    (net (code "74") (name "unconnected-(U4-VREF-{slash}VeREF--Pad11)") (class "Default")
      (node (ref "U4") (pin "11") (pinfunction "VREF-/VeREF-_11") (pintype "passive+no_connect"))
    )
    (net (code "75") (name "unconnected-(U4-VeREF+-Pad10)") (class "Default")
      (node (ref "U4") (pin "10") (pinfunction "VeREF+_10") (pintype "passive+no_connect"))
    )
    (net (code "76") (name "unconnected-(U4-XOUT-Pad9)") (class "Default")
      (node (ref "U4") (pin "9") (pinfunction "XOUT_9") (pintype "passive+no_connect"))
    )
    (net (code "77") (name "unconnected-(U4-XT2IN-Pad53)") (class "Default")
      (node (ref "U4") (pin "53") (pinfunction "XT2IN_53") (pintype "passive+no_connect"))
    )
    (net (code "78") (name "unconnected-(U4-XT2OUT-Pad52)") (class "Default")
      (node (ref "U4") (pin "52") (pinfunction "XT2OUT_52") (pintype "passive+no_connect"))
    )
  )
)
